# motor.net
KiCad netlist of a schematic drawn in EAGLE
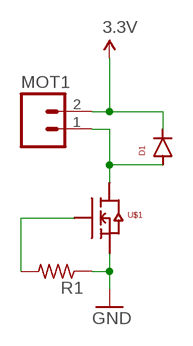
[diagram p0: schematic, sheet 1]

(export (version "E")
  (design (tool "Eeschema 10.0.6"))
  (components
    (comp (ref "D1")
      (value "DIODE")
      (footprint "eagle-import:DIODE")
      (libsource (lib "eagle-import") (part "DIODE"))
    )
    (comp (ref "MOT1")
      (value "M02PTH")
      (footprint "eagle-import:1X02")
      (libsource (lib "eagle-import") (part "M02PTH"))
    )
    (comp (ref "R1")
      (value "R-US_R0805")
      (footprint "eagle-import:R0805")
      (libsource (lib "eagle-import") (part "R-US_R0805"))
    )
    (comp (ref "U$1")
      (value "FET")
      (footprint "eagle-import:FET")
      (libsource (lib "eagle-import") (part "FET"))
    )
  )
  (nets
    (net (code "1") (name "3.3V") (class "Default")
      (node (ref "D1") (pin "P$NEG") (pinfunction "P$NEG_P$NEG") (pintype "bidirectional"))
      (node (ref "MOT1") (pin "2") (pinfunction "2_2") (pintype "passive"))
    )
    (net (code "2") (name "GND") (class "Default")
      (node (ref "R1") (pin "1") (pinfunction "1_1") (pintype "passive"))
      (node (ref "U$1") (pin "P$2") (pinfunction "P$2_P$2") (pintype "bidirectional"))
    )
    (net (code "3") (name "Net-(D1-PadP$POS)") (class "Default")
      (node (ref "D1") (pin "P$POS") (pinfunction "P$POS_P$POS") (pintype "bidirectional"))
      (node (ref "MOT1") (pin "1") (pinfunction "1_1") (pintype "passive"))
      (node (ref "U$1") (pin "P$3") (pinfunction "P$3_P$3") (pintype "bidirectional"))
    )
    (net (code "4") (name "Net-(R1-Pad2)") (class "Default")
      (node (ref "R1") (pin "2") (pinfunction "2_2") (pintype "passive"))
      (node (ref "U$1") (pin "P$1") (pinfunction "P$1_P$1") (pintype "bidirectional"))
    )
  )
)
